# Garage_PCB.net
KiCad netlist of a schematic drawn in EAGLE
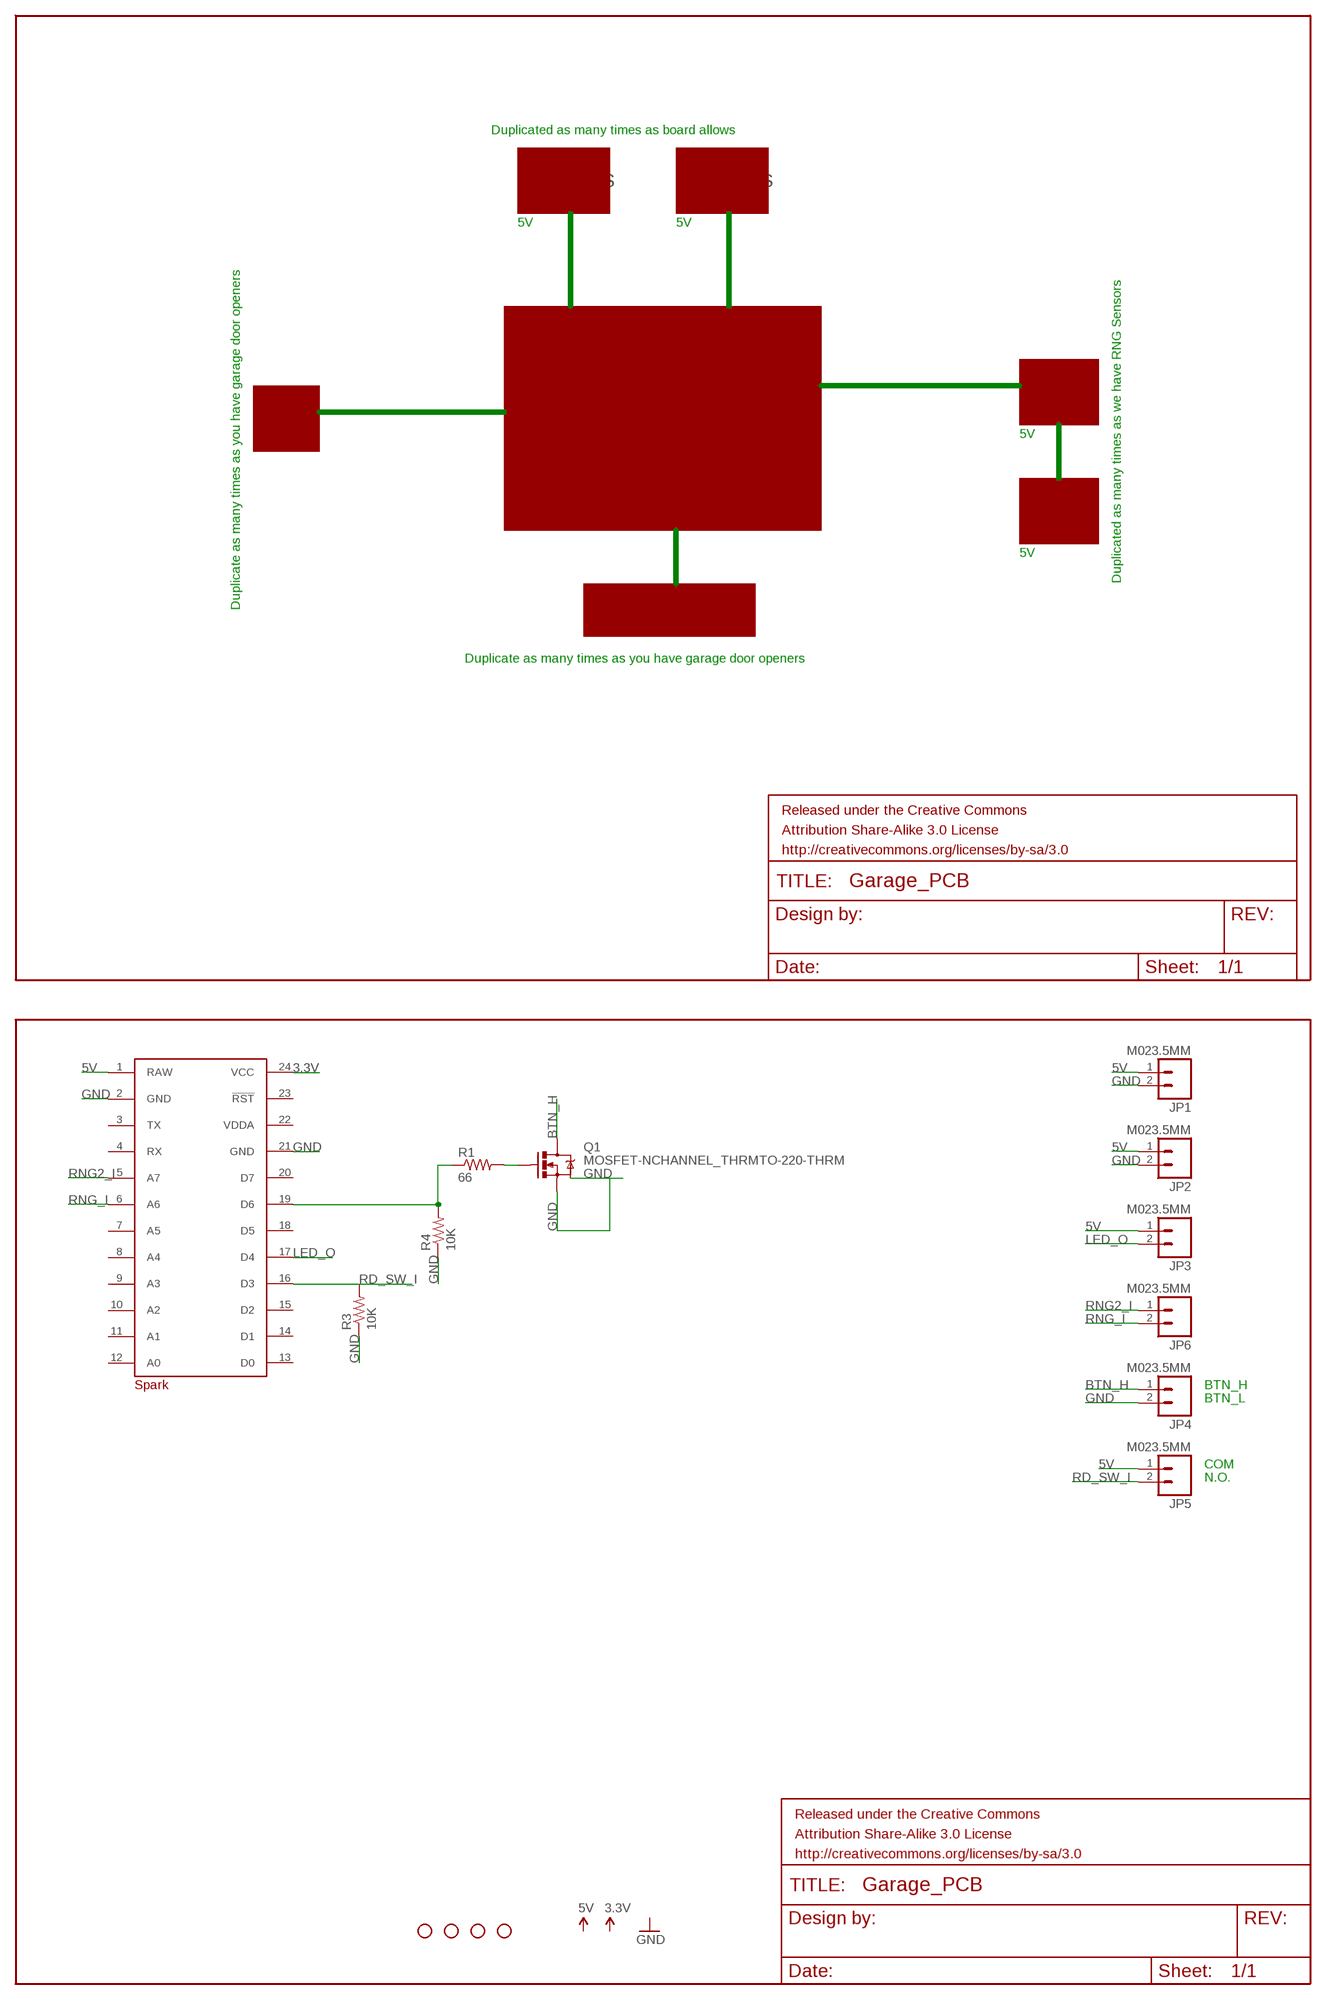
[diagram p0: schematic, sheet 1]

(export (version "E")
  (design (tool "Eeschema 10.0.6"))
  (components
    (comp (ref "FRAME1")
      (value "FRAME-LETTER")
      (footprint "eagle-import:CREATIVE_COMMONS")
      (libsource (lib "eagle-import") (part "FRAME-LETTER"))
    )
    (comp (ref "FRAME2")
      (value "FRAME-LETTER")
      (footprint "eagle-import:CREATIVE_COMMONS")
      (libsource (lib "eagle-import") (part "FRAME-LETTER"))
    )
    (comp (ref "JP1")
      (value "M023.5MM")
      (footprint "eagle-import:SCREWTERMINAL-3.5MM-2")
      (libsource (lib "eagle-import") (part "M023.5MM"))
    )
    (comp (ref "JP2")
      (value "M023.5MM")
      (footprint "eagle-import:SCREWTERMINAL-3.5MM-2")
      (libsource (lib "eagle-import") (part "M023.5MM"))
    )
    (comp (ref "JP3")
      (value "M023.5MM")
      (footprint "eagle-import:SCREWTERMINAL-3.5MM-2")
      (libsource (lib "eagle-import") (part "M023.5MM"))
    )
    (comp (ref "JP4")
      (value "M023.5MM")
      (footprint "eagle-import:SCREWTERMINAL-3.5MM-2")
      (libsource (lib "eagle-import") (part "M023.5MM"))
    )
    (comp (ref "JP5")
      (value "M023.5MM")
      (footprint "eagle-import:SCREWTERMINAL-3.5MM-2")
      (libsource (lib "eagle-import") (part "M023.5MM"))
    )
    (comp (ref "JP6")
      (value "M023.5MM")
      (footprint "eagle-import:SCREWTERMINAL-3.5MM-2")
      (libsource (lib "eagle-import") (part "M023.5MM"))
    )
    (comp (ref "Q1")
      (value "MOSFET-NCHANNEL_THRMTO-220-THRM")
      (footprint "eagle-import:TO220-THRM")
      (libsource (lib "eagle-import") (part "MOSFET-NCHANNEL_THRMTO-220-THRM"))
    )
    (comp (ref "R1")
      (value "66")
      (footprint "eagle-import:0603-RES")
      (libsource (lib "eagle-import") (part "RESISTOR0603"))
    )
    (comp (ref "R3")
      (value "10K")
      (footprint "eagle-import:0603-RES")
      (libsource (lib "eagle-import") (part "RESISTOR0603"))
    )
    (comp (ref "R4")
      (value "10K")
      (footprint "eagle-import:0603-RES")
      (libsource (lib "eagle-import") (part "RESISTOR0603"))
    )
    (comp (ref "SPARK")
      (value "SPARK_CORECORE")
      (footprint "eagle-import:SPARK_CORE")
      (libsource (lib "eagle-import") (part "SPARK_CORECORE"))
    )
    (comp (ref "STANDOFF1")
      (value "STAND-OFF")
      (footprint "eagle-import:STAND-OFF")
      (libsource (lib "eagle-import") (part "STAND-OFF"))
    )
    (comp (ref "STANDOFF2")
      (value "STAND-OFF")
      (footprint "eagle-import:STAND-OFF")
      (libsource (lib "eagle-import") (part "STAND-OFF"))
    )
    (comp (ref "STANDOFF3")
      (value "STAND-OFF")
      (footprint "eagle-import:STAND-OFF")
      (libsource (lib "eagle-import") (part "STAND-OFF"))
    )
    (comp (ref "STANDOFF4")
      (value "STAND-OFF")
      (footprint "eagle-import:STAND-OFF")
      (libsource (lib "eagle-import") (part "STAND-OFF"))
    )
    (comp (ref "U$2")
      (value "SPARK_LOGO2")
      (footprint "eagle-import:SPARK_LOGO2")
      (libsource (lib "eagle-import") (part "SPARK_LOGO2"))
    )
  )
  (nets
    (net (code "1") (name "/BTN_H") (class "Default")
      (node (ref "JP4") (pin "1") (pinfunction "1_1") (pintype "passive"))
      (node (ref "Q1") (pin "GND") (pinfunction "D_GND") (pintype "passive"))
    )
    (net (code "2") (name "/LED_O") (class "Default")
      (node (ref "JP3") (pin "2") (pinfunction "2_2") (pintype "passive"))
      (node (ref "SPARK") (pin "17") (pinfunction "D4_17") (pintype "bidirectional"))
    )
    (net (code "3") (name "/RD_SW_I") (class "Default")
      (node (ref "JP5") (pin "2") (pinfunction "2_2") (pintype "passive"))
      (node (ref "R3") (pin "2") (pinfunction "2_2") (pintype "passive"))
      (node (ref "SPARK") (pin "16") (pinfunction "D3_16") (pintype "bidirectional"))
    )
    (net (code "4") (name "/RNG2_I") (class "Default")
      (node (ref "JP6") (pin "1") (pinfunction "1_1") (pintype "passive"))
      (node (ref "SPARK") (pin "5") (pinfunction "A7_5") (pintype "bidirectional"))
    )
    (net (code "5") (name "/RNG_I") (class "Default")
      (node (ref "JP6") (pin "2") (pinfunction "2_2") (pintype "passive"))
      (node (ref "SPARK") (pin "6") (pinfunction "A6_6") (pintype "bidirectional"))
    )
    (net (code "6") (name "/VDDA") (class "Default")
      (node (ref "SPARK") (pin "22") (pinfunction "VDDA_22") (pintype "power_in"))
    )
    (net (code "7") (name "3.3V") (class "Default")
      (node (ref "SPARK") (pin "24") (pinfunction "VCC_24") (pintype "power_in"))
    )
    (net (code "8") (name "5V") (class "Default")
      (node (ref "JP1") (pin "1") (pinfunction "1_1") (pintype "passive"))
      (node (ref "JP2") (pin "1") (pinfunction "1_1") (pintype "passive"))
      (node (ref "JP3") (pin "1") (pinfunction "1_1") (pintype "passive"))
      (node (ref "JP5") (pin "1") (pinfunction "1_1") (pintype "passive"))
      (node (ref "SPARK") (pin "1") (pinfunction "RAW_1") (pintype "power_in"))
    )
    (net (code "9") (name "GND") (class "Default")
      (node (ref "JP1") (pin "2") (pinfunction "2_2") (pintype "passive"))
      (node (ref "JP2") (pin "2") (pinfunction "2_2") (pintype "passive"))
      (node (ref "JP4") (pin "2") (pinfunction "2_2") (pintype "passive"))
      (node (ref "Q1") (pin "OUT") (pinfunction "S_OUT") (pintype "passive"))
      (node (ref "Q1") (pin "THRM") (pinfunction "THRM_THRM") (pintype "passive"))
      (node (ref "R3") (pin "1") (pinfunction "1_1") (pintype "passive"))
      (node (ref "R4") (pin "1") (pinfunction "1_1") (pintype "passive"))
      (node (ref "SPARK") (pin "2") (pinfunction "GND_2") (pintype "power_in"))
      (node (ref "SPARK") (pin "21") (pinfunction "GND_21") (pintype "power_in"))
    )
    (net (code "10") (name "Net-(Q1-G)") (class "Default")
      (node (ref "Q1") (pin "IN") (pinfunction "G_IN") (pintype "passive"))
      (node (ref "R1") (pin "2") (pinfunction "2_2") (pintype "passive"))
    )
    (net (code "11") (name "Net-(SPARK-D6)") (class "Default")
      (node (ref "R1") (pin "1") (pinfunction "1_1") (pintype "passive"))
      (node (ref "R4") (pin "2") (pinfunction "2_2") (pintype "passive"))
      (node (ref "SPARK") (pin "19") (pinfunction "D6_19") (pintype "bidirectional"))
    )
    (net (code "12") (name "unconnected-(SPARK-A0-Pad12)") (class "Default")
      (node (ref "SPARK") (pin "12") (pinfunction "A0_12") (pintype "bidirectional"))
    )
    (net (code "13") (name "unconnected-(SPARK-A1-Pad11)") (class "Default")
      (node (ref "SPARK") (pin "11") (pinfunction "A1_11") (pintype "bidirectional"))
    )
    (net (code "14") (name "unconnected-(SPARK-A2-Pad10)") (class "Default")
      (node (ref "SPARK") (pin "10") (pinfunction "A2_10") (pintype "bidirectional"))
    )
    (net (code "15") (name "unconnected-(SPARK-A3-Pad9)") (class "Default")
      (node (ref "SPARK") (pin "9") (pinfunction "A3_9") (pintype "bidirectional"))
    )
    (net (code "16") (name "unconnected-(SPARK-A4-Pad8)") (class "Default")
      (node (ref "SPARK") (pin "8") (pinfunction "A4_8") (pintype "bidirectional"))
    )
    (net (code "17") (name "unconnected-(SPARK-A5-Pad7)") (class "Default")
      (node (ref "SPARK") (pin "7") (pinfunction "A5_7") (pintype "bidirectional"))
    )
    (net (code "18") (name "unconnected-(SPARK-D0-Pad13)") (class "Default")
      (node (ref "SPARK") (pin "13") (pinfunction "D0_13") (pintype "bidirectional"))
    )
    (net (code "19") (name "unconnected-(SPARK-D1-Pad14)") (class "Default")
      (node (ref "SPARK") (pin "14") (pinfunction "D1_14") (pintype "bidirectional"))
    )
    (net (code "20") (name "unconnected-(SPARK-D2-Pad15)") (class "Default")
      (node (ref "SPARK") (pin "15") (pinfunction "D2_15") (pintype "bidirectional"))
    )
    (net (code "21") (name "unconnected-(SPARK-D5-Pad18)") (class "Default")
      (node (ref "SPARK") (pin "18") (pinfunction "D5_18") (pintype "bidirectional"))
    )
    (net (code "22") (name "unconnected-(SPARK-D7-Pad20)") (class "Default")
      (node (ref "SPARK") (pin "20") (pinfunction "D7_20") (pintype "bidirectional"))
    )
    (net (code "23") (name "unconnected-(SPARK-RX-Pad4)") (class "Default")
      (node (ref "SPARK") (pin "4") (pinfunction "RX_4") (pintype "bidirectional"))
    )
    (net (code "24") (name "unconnected-(SPARK-TX-Pad3)") (class "Default")
      (node (ref "SPARK") (pin "3") (pinfunction "TX_3") (pintype "bidirectional"))
    )
    (net (code "25") (name "unconnected-(SPARK-~{RST}-Pad23)") (class "Default")
      (node (ref "SPARK") (pin "23") (pinfunction "~{RST}_23") (pintype "bidirectional"))
    )
  )
)
